# stm_board.net
KiCad netlist of a schematic drawn in EAGLE
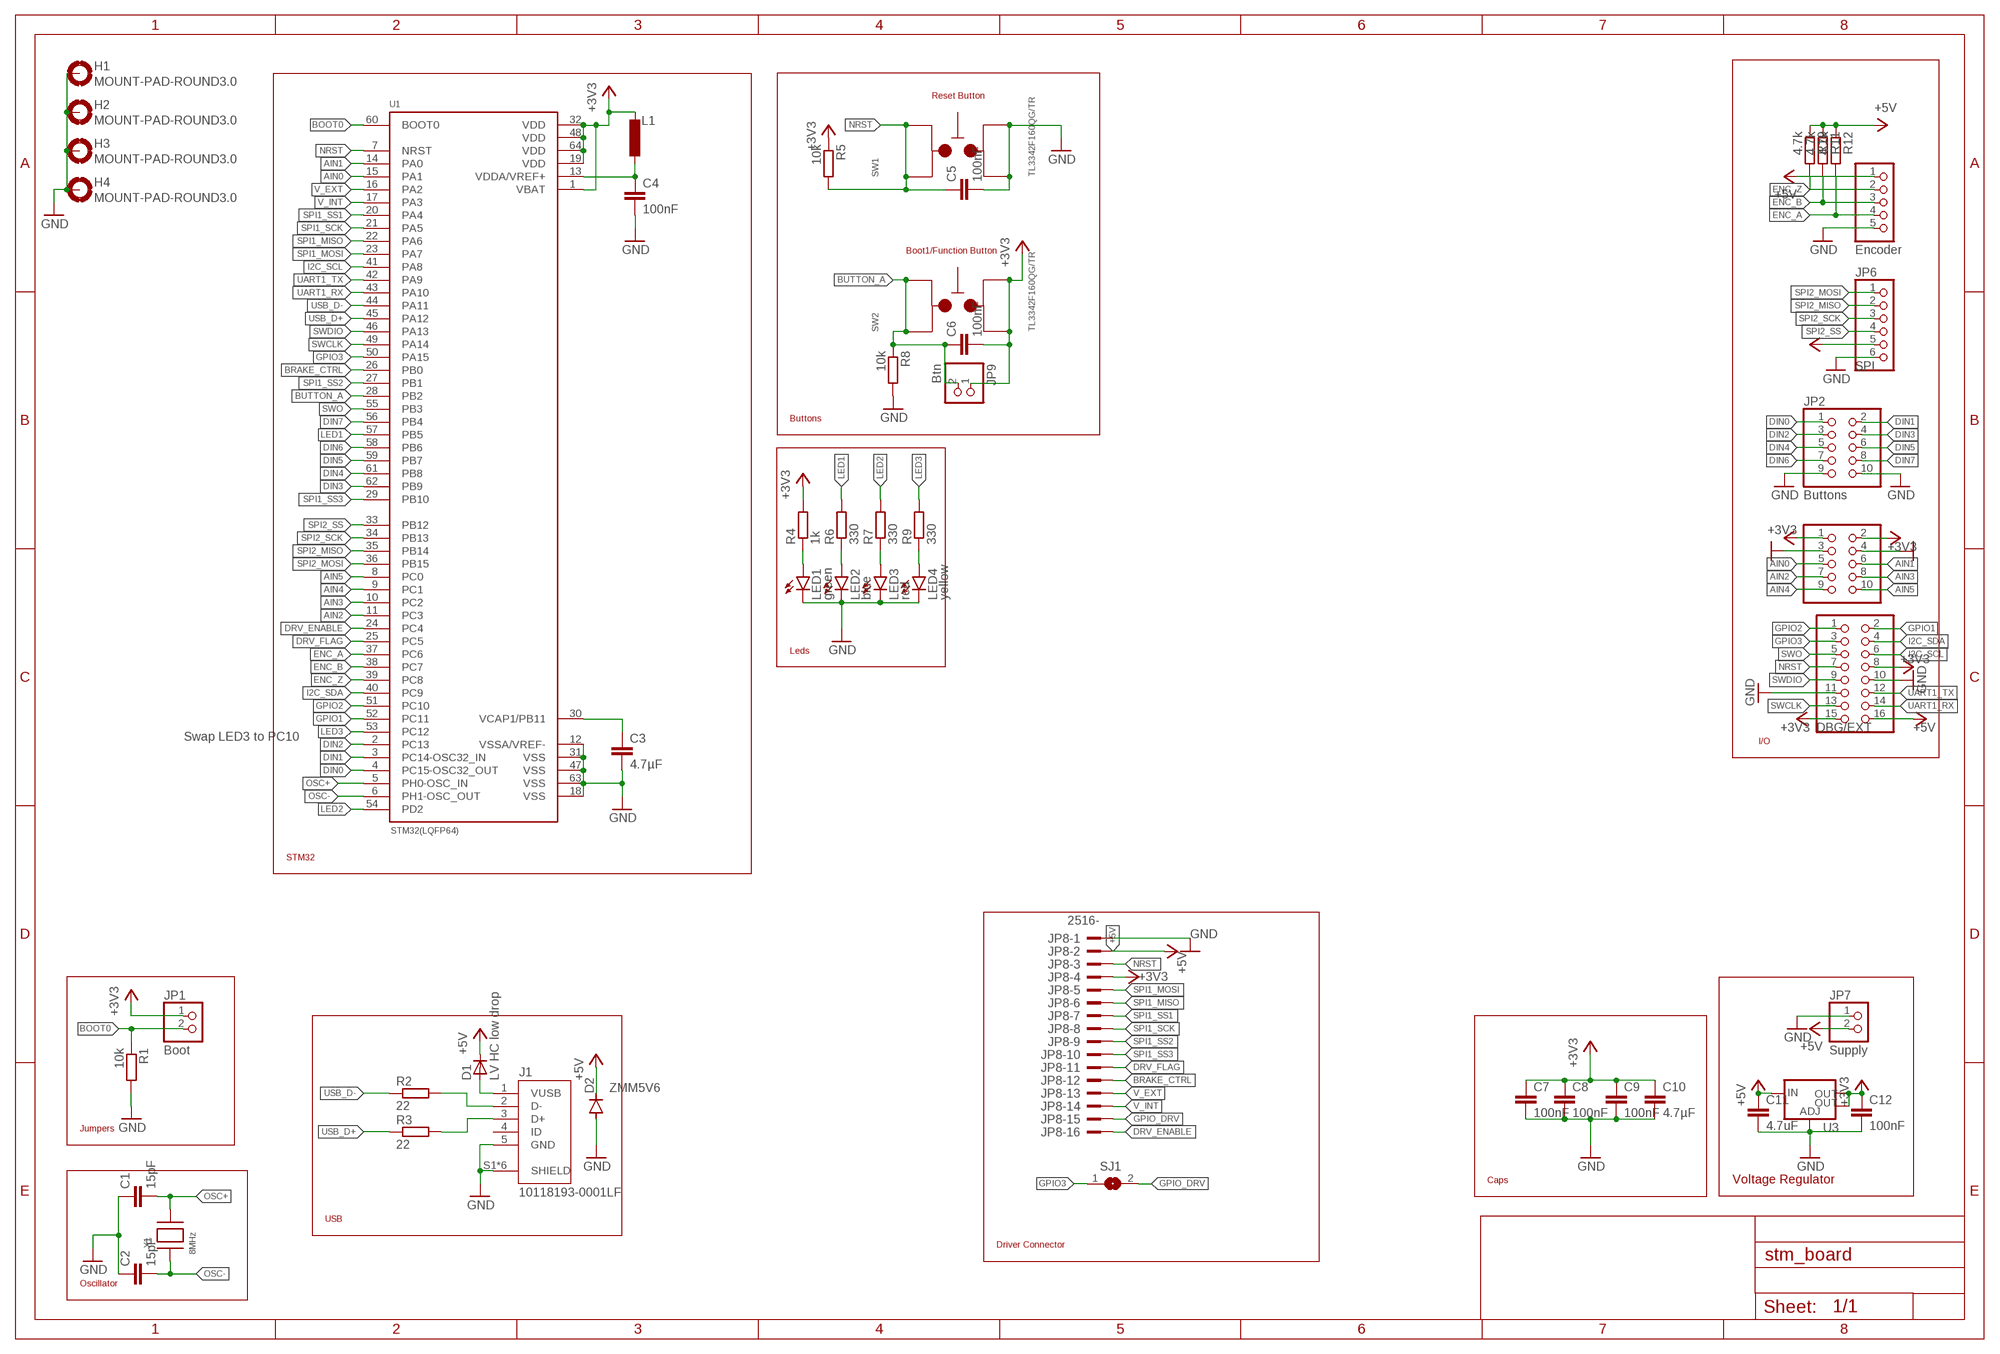
[diagram p0: schematic, sheet 1]

(export (version "E")
  (design (tool "Eeschema 10.0.6"))
  (components
    (comp (ref "C1")
      (value "15pF")
      (footprint "eagle-import:C0603")
      (libsource (lib "eagle-import") (part "C-EUC0603"))
    )
    (comp (ref "C2")
      (value "15pF")
      (footprint "eagle-import:C0603")
      (libsource (lib "eagle-import") (part "C-EUC0603"))
    )
    (comp (ref "C3")
      (value "4.7µF")
      (footprint "eagle-import:C0805")
      (libsource (lib "eagle-import") (part "C-EUC0805"))
    )
    (comp (ref "C4")
      (value "100nF")
      (footprint "eagle-import:C0603")
      (libsource (lib "eagle-import") (part "C-EUC0603"))
    )
    (comp (ref "C5")
      (value "100nF")
      (footprint "eagle-import:C0603")
      (libsource (lib "eagle-import") (part "C-EUC0603"))
    )
    (comp (ref "C6")
      (value "100nF")
      (footprint "eagle-import:C0603")
      (libsource (lib "eagle-import") (part "C-EUC0603"))
    )
    (comp (ref "C7")
      (value "100nF")
      (footprint "eagle-import:C0603")
      (libsource (lib "eagle-import") (part "C-EUC0603"))
    )
    (comp (ref "C8")
      (value "100nF")
      (footprint "eagle-import:C0603")
      (libsource (lib "eagle-import") (part "C-EUC0603"))
    )
    (comp (ref "C9")
      (value "100nF")
      (footprint "eagle-import:C0603")
      (libsource (lib "eagle-import") (part "C-EUC0603"))
    )
    (comp (ref "C10")
      (value "4.7µF")
      (footprint "eagle-import:C0805")
      (libsource (lib "eagle-import") (part "C-EUC0805"))
    )
    (comp (ref "C11")
      (value "4.7uF")
      (footprint "eagle-import:C0805")
      (libsource (lib "eagle-import") (part "C-EUC0805"))
    )
    (comp (ref "C12")
      (value "100nF")
      (footprint "eagle-import:C0603")
      (libsource (lib "eagle-import") (part "C-EUC0603"))
    )
    (comp (ref "D1")
      (value "LV HC low drop")
      (footprint "eagle-import:SMADIODE")
      (libsource (lib "eagle-import") (part "DIODESMA"))
    )
    (comp (ref "D2")
      (value "ZMM5V6")
      (footprint "eagle-import:MINIMELF")
      (libsource (lib "eagle-import") (part "DIODE-MINIMELF"))
    )
    (comp (ref "H1")
      (value "MOUNT-PAD-ROUND3.0")
      (footprint "eagle-import:3,0-PAD")
      (libsource (lib "eagle-import") (part "MOUNT-PAD-ROUND3.0"))
    )
    (comp (ref "H2")
      (value "MOUNT-PAD-ROUND3.0")
      (footprint "eagle-import:3,0-PAD")
      (libsource (lib "eagle-import") (part "MOUNT-PAD-ROUND3.0"))
    )
    (comp (ref "H3")
      (value "MOUNT-PAD-ROUND3.0")
      (footprint "eagle-import:3,0-PAD")
      (libsource (lib "eagle-import") (part "MOUNT-PAD-ROUND3.0"))
    )
    (comp (ref "H4")
      (value "MOUNT-PAD-ROUND3.0")
      (footprint "eagle-import:3,0-PAD")
      (libsource (lib "eagle-import") (part "MOUNT-PAD-ROUND3.0"))
    )
    (comp (ref "J1")
      (value "10118193-0001LF")
      (footprint "eagle-import:FCI_10118193-0001LF")
      (fields (field (name "MF") "Amphenol ICC"))
      (libsource (lib "eagle-import") (part "10118193-0001LF"))
    )
    (comp (ref "JP1")
      (value "Boot")
      (footprint "eagle-import:1X02")
      (libsource (lib "eagle-import") (part "PINHD-1X2"))
    )
    (comp (ref "JP2")
      (value "Buttons")
      (footprint "eagle-import:2X05")
      (libsource (lib "eagle-import") (part "PINHD-2X5"))
    )
    (comp (ref "JP3")
      (value "Analog")
      (footprint "eagle-import:2X05")
      (libsource (lib "eagle-import") (part "PINHD-2X5"))
    )
    (comp (ref "JP4")
      (value "DBG/EXT")
      (footprint "eagle-import:2X08")
      (libsource (lib "eagle-import") (part "PINHD-2X8"))
    )
    (comp (ref "JP5")
      (value "Encoder")
      (footprint "eagle-import:1X05")
      (libsource (lib "eagle-import") (part "PINHD-1X5"))
    )
    (comp (ref "JP6")
      (value "SPI")
      (footprint "eagle-import:1X06")
      (libsource (lib "eagle-import") (part "PINHD-1X6"))
    )
    (comp (ref "JP7")
      (value "Supply")
      (footprint "eagle-import:1X02")
      (libsource (lib "eagle-import") (part "PINHD-1X2"))
    )
    (comp (ref "JP8")
      (value "2516-")
      (footprint "eagle-import:PAK100_2500-16")
      (libsource (lib "eagle-import") (part "2516-"))
    )
    (comp (ref "JP9")
      (value "Btn")
      (footprint "eagle-import:1X02")
      (libsource (lib "eagle-import") (part "PINHD-1X2"))
    )
    (comp (ref "L1")
      (value "2.2µH")
      (footprint "eagle-import:L2012C")
      (libsource (lib "eagle-import") (part "L-EUL2012C"))
    )
    (comp (ref "LED1")
      (value "green")
      (footprint "eagle-import:CHIPLED_0805")
      (libsource (lib "eagle-import") (part "LEDCHIPLED_0805"))
    )
    (comp (ref "LED2")
      (value "blue")
      (footprint "eagle-import:CHIPLED_0805")
      (libsource (lib "eagle-import") (part "LEDCHIPLED_0805"))
    )
    (comp (ref "LED3")
      (value "red")
      (footprint "eagle-import:CHIPLED_0805")
      (libsource (lib "eagle-import") (part "LEDCHIPLED_0805"))
    )
    (comp (ref "LED4")
      (value "yellow")
      (footprint "eagle-import:CHIPLED_0805")
      (libsource (lib "eagle-import") (part "LEDCHIPLED_0805"))
    )
    (comp (ref "R1")
      (value "10k")
      (footprint "eagle-import:R0603")
      (libsource (lib "eagle-import") (part "R-EU_R0603"))
    )
    (comp (ref "R2")
      (value "22")
      (footprint "eagle-import:R0603")
      (libsource (lib "eagle-import") (part "R-EU_R0603"))
    )
    (comp (ref "R3")
      (value "22")
      (footprint "eagle-import:R0603")
      (libsource (lib "eagle-import") (part "R-EU_R0603"))
    )
    (comp (ref "R4")
      (value "1k")
      (footprint "eagle-import:R0603")
      (libsource (lib "eagle-import") (part "R-EU_R0603"))
    )
    (comp (ref "R5")
      (value "10k")
      (footprint "eagle-import:R0603")
      (libsource (lib "eagle-import") (part "R-EU_R0603"))
    )
    (comp (ref "R6")
      (value "330")
      (footprint "eagle-import:R0603")
      (libsource (lib "eagle-import") (part "R-EU_R0603"))
    )
    (comp (ref "R7")
      (value "330")
      (footprint "eagle-import:R0603")
      (libsource (lib "eagle-import") (part "R-EU_R0603"))
    )
    (comp (ref "R8")
      (value "10k")
      (footprint "eagle-import:R0603")
      (libsource (lib "eagle-import") (part "R-EU_R0603"))
    )
    (comp (ref "R9")
      (value "330")
      (footprint "eagle-import:R0603")
      (libsource (lib "eagle-import") (part "R-EU_R0603"))
    )
    (comp (ref "R10")
      (value "4.7k")
      (footprint "eagle-import:R0603")
      (libsource (lib "eagle-import") (part "R-EU_R0603"))
    )
    (comp (ref "R11")
      (value "4.7k")
      (footprint "eagle-import:R0603")
      (libsource (lib "eagle-import") (part "R-EU_R0603"))
    )
    (comp (ref "R12")
      (value "4.7k")
      (footprint "eagle-import:R0603")
      (libsource (lib "eagle-import") (part "R-EU_R0603"))
    )
    (comp (ref "SJ1") (value "SJ") (footprint "eagle-import:SJ") (libsource (lib "eagle-import") (part "SJ")))
    (comp (ref "SW1")
      (value "TL3342F160QG/TR")
      (footprint "eagle-import:TL3342F160QG_TR")
      (fields
        (field (name "DIGI_KEY_PART_NUMBER") "EG2531CT-ND")
        (field (name "MANUFACTURER") "E-Switch")
        (field (name "CREATED_BY") "PCBLayout.com")
      )
      (libsource (lib "eagle-import") (part "TL3342F160QG/TR"))
    )
    (comp (ref "SW2")
      (value "TL3342F160QG/TR")
      (footprint "eagle-import:TL3342F160QG_TR")
      (fields
        (field (name "DIGI_KEY_PART_NUMBER") "EG2531CT-ND")
        (field (name "MANUFACTURER") "E-Switch")
        (field (name "CREATED_BY") "PCBLayout.com")
      )
      (libsource (lib "eagle-import") (part "TL3342F160QG/TR"))
    )
    (comp (ref "U1")
      (value "STM32(LQFP64)")
      (footprint "eagle-import:QFP50P1200X1200X160-64N")
      (fields (field (name "MF") "STMicroelectronics") (field (name "MP") "STM32"))
      (libsource (lib "eagle-import") (part "STM32(LQFP64)"))
    )
    (comp (ref "U3")
      (value "V_REG_LM1117SOT223")
      (footprint "eagle-import:SOT223")
      (libsource (lib "eagle-import") (part "V_REG_LM1117SOT223"))
    )
    (comp (ref "X1")
      (value "8MHz")
      (footprint "eagle-import:NX5032")
      (libsource (lib "eagle-import") (part "XTALNX5032"))
    )
  )
  (nets
    (net (code "1") (name "+3V3") (class "Default")
      (node (ref "C10") (pin "1") (pinfunction "1_1") (pintype "passive"))
      (node (ref "C12") (pin "1") (pinfunction "1_1") (pintype "passive"))
      (node (ref "C6") (pin "2") (pinfunction "2_2") (pintype "passive"))
      (node (ref "C7") (pin "1") (pinfunction "1_1") (pintype "passive"))
      (node (ref "C8") (pin "1") (pinfunction "1_1") (pintype "passive"))
      (node (ref "C9") (pin "1") (pinfunction "1_1") (pintype "passive"))
      (node (ref "JP1") (pin "1") (pinfunction "1_1") (pintype "passive"))
      (node (ref "JP3") (pin "1") (pinfunction "1_1") (pintype "passive"))
      (node (ref "JP3") (pin "2") (pinfunction "2_2") (pintype "passive"))
      (node (ref "JP4") (pin "15") (pinfunction "15_15") (pintype "passive"))
      (node (ref "JP4") (pin "8") (pinfunction "8_8") (pintype "passive"))
      (node (ref "JP6") (pin "5") (pinfunction "5_5") (pintype "passive"))
      (node (ref "JP8") (pin "4") (pinfunction "KL_4") (pintype "passive"))
      (node (ref "JP9") (pin "1") (pinfunction "1_1") (pintype "passive"))
      (node (ref "L1") (pin "1") (pinfunction "1_1") (pintype "passive"))
      (node (ref "R4") (pin "2") (pinfunction "2_2") (pintype "passive"))
      (node (ref "R5") (pin "1") (pinfunction "1_1") (pintype "passive"))
      (node (ref "SW2") (pin "1") (pinfunction "1_1") (pintype "passive"))
      (node (ref "SW2") (pin "2") (pinfunction "2_2") (pintype "passive"))
      (node (ref "U1") (pin "1") (pinfunction "VBAT_1") (pintype "power_in"))
      (node (ref "U1") (pin "19") (pinfunction "VDD_19") (pintype "power_in"))
      (node (ref "U1") (pin "32") (pinfunction "VDD_32") (pintype "power_in"))
      (node (ref "U1") (pin "48") (pinfunction "VDD_48") (pintype "power_in"))
      (node (ref "U1") (pin "64") (pinfunction "VDD_64") (pintype "power_in"))
      (node (ref "U3") (pin "2") (pinfunction "OUT_2") (pintype "output"))
      (node (ref "U3") (pin "4") (pinfunction "OUT_4") (pintype "output"))
    )
    (net (code "2") (name "+5V") (class "Default")
      (node (ref "C11") (pin "1") (pinfunction "1_1") (pintype "passive"))
      (node (ref "D1") (pin "C") (pinfunction "C_C") (pintype "passive"))
      (node (ref "D2") (pin "C") (pinfunction "C_C") (pintype "passive"))
      (node (ref "JP4") (pin "16") (pinfunction "16_16") (pintype "passive"))
      (node (ref "JP5") (pin "1") (pinfunction "1_1") (pintype "passive"))
      (node (ref "JP7") (pin "2") (pinfunction "2_2") (pintype "passive"))
      (node (ref "JP8") (pin "2") (pinfunction "KL_2") (pintype "passive"))
      (node (ref "R10") (pin "1") (pinfunction "1_1") (pintype "passive"))
      (node (ref "R11") (pin "1") (pinfunction "1_1") (pintype "passive"))
      (node (ref "R12") (pin "1") (pinfunction "1_1") (pintype "passive"))
      (node (ref "U3") (pin "3") (pinfunction "IN_3") (pintype "input"))
    )
    (net (code "3") (name "AIN0") (class "Default")
      (node (ref "JP3") (pin "5") (pinfunction "5_5") (pintype "passive"))
      (node (ref "U1") (pin "15") (pinfunction "PA1_15") (pintype "bidirectional"))
    )
    (net (code "4") (name "AIN1") (class "Default")
      (node (ref "JP3") (pin "6") (pinfunction "6_6") (pintype "passive"))
      (node (ref "U1") (pin "14") (pinfunction "PA0_14") (pintype "bidirectional"))
    )
    (net (code "5") (name "AIN2") (class "Default")
      (node (ref "JP3") (pin "7") (pinfunction "7_7") (pintype "passive"))
      (node (ref "U1") (pin "11") (pinfunction "PC3_11") (pintype "bidirectional"))
    )
    (net (code "6") (name "AIN3") (class "Default")
      (node (ref "JP3") (pin "8") (pinfunction "8_8") (pintype "passive"))
      (node (ref "U1") (pin "10") (pinfunction "PC2_10") (pintype "bidirectional"))
    )
    (net (code "7") (name "AIN4") (class "Default")
      (node (ref "JP3") (pin "9") (pinfunction "9_9") (pintype "passive"))
      (node (ref "U1") (pin "9") (pinfunction "PC1_9") (pintype "bidirectional"))
    )
    (net (code "8") (name "AIN5") (class "Default")
      (node (ref "JP3") (pin "10") (pinfunction "10_10") (pintype "passive"))
      (node (ref "U1") (pin "8") (pinfunction "PC0_8") (pintype "bidirectional"))
    )
    (net (code "9") (name "BOOT0") (class "Default")
      (node (ref "JP1") (pin "2") (pinfunction "2_2") (pintype "passive"))
      (node (ref "R1") (pin "1") (pinfunction "1_1") (pintype "passive"))
      (node (ref "U1") (pin "60") (pinfunction "BOOT0_60") (pintype "input"))
    )
    (net (code "10") (name "BRAKE_CTRL") (class "Default")
      (node (ref "JP8") (pin "12") (pinfunction "KL_12") (pintype "passive"))
      (node (ref "U1") (pin "26") (pinfunction "PB0_26") (pintype "bidirectional"))
    )
    (net (code "11") (name "BUTTON_A") (class "Default")
      (node (ref "C6") (pin "1") (pinfunction "1_1") (pintype "passive"))
      (node (ref "JP9") (pin "2") (pinfunction "2_2") (pintype "passive"))
      (node (ref "R8") (pin "1") (pinfunction "1_1") (pintype "passive"))
      (node (ref "SW2") (pin "3") (pinfunction "3_3") (pintype "passive"))
      (node (ref "SW2") (pin "4") (pinfunction "4_4") (pintype "passive"))
      (node (ref "U1") (pin "28") (pinfunction "PB2_28") (pintype "bidirectional"))
    )
    (net (code "12") (name "DIN0") (class "Default")
      (node (ref "JP2") (pin "1") (pinfunction "1_1") (pintype "passive"))
      (node (ref "U1") (pin "4") (pinfunction "PC15-OSC32_OUT_4") (pintype "bidirectional"))
    )
    (net (code "13") (name "DIN1") (class "Default")
      (node (ref "JP2") (pin "2") (pinfunction "2_2") (pintype "passive"))
      (node (ref "U1") (pin "3") (pinfunction "PC14-OSC32_IN_3") (pintype "bidirectional"))
    )
    (net (code "14") (name "DIN2") (class "Default")
      (node (ref "JP2") (pin "3") (pinfunction "3_3") (pintype "passive"))
      (node (ref "U1") (pin "2") (pinfunction "PC13_2") (pintype "bidirectional"))
    )
    (net (code "15") (name "DIN3") (class "Default")
      (node (ref "JP2") (pin "4") (pinfunction "4_4") (pintype "passive"))
      (node (ref "U1") (pin "62") (pinfunction "PB9_62") (pintype "bidirectional"))
    )
    (net (code "16") (name "DIN4") (class "Default")
      (node (ref "JP2") (pin "5") (pinfunction "5_5") (pintype "passive"))
      (node (ref "U1") (pin "61") (pinfunction "PB8_61") (pintype "bidirectional"))
    )
    (net (code "17") (name "DIN5") (class "Default")
      (node (ref "JP2") (pin "6") (pinfunction "6_6") (pintype "passive"))
      (node (ref "U1") (pin "59") (pinfunction "PB7_59") (pintype "bidirectional"))
    )
    (net (code "18") (name "DIN6") (class "Default")
      (node (ref "JP2") (pin "7") (pinfunction "7_7") (pintype "passive"))
      (node (ref "U1") (pin "58") (pinfunction "PB6_58") (pintype "bidirectional"))
    )
    (net (code "19") (name "DIN7") (class "Default")
      (node (ref "JP2") (pin "8") (pinfunction "8_8") (pintype "passive"))
      (node (ref "U1") (pin "56") (pinfunction "PB4_56") (pintype "bidirectional"))
    )
    (net (code "20") (name "DRV_ENABLE") (class "Default")
      (node (ref "JP8") (pin "16") (pinfunction "KL_16") (pintype "passive"))
      (node (ref "U1") (pin "24") (pinfunction "PC4_24") (pintype "bidirectional"))
    )
    (net (code "21") (name "DRV_FLAG") (class "Default")
      (node (ref "JP8") (pin "11") (pinfunction "KL_11") (pintype "passive"))
      (node (ref "U1") (pin "25") (pinfunction "PC5_25") (pintype "bidirectional"))
    )
    (net (code "22") (name "ENC_A") (class "Default")
      (node (ref "JP5") (pin "4") (pinfunction "4_4") (pintype "passive"))
      (node (ref "R12") (pin "2") (pinfunction "2_2") (pintype "passive"))
      (node (ref "U1") (pin "37") (pinfunction "PC6_37") (pintype "bidirectional"))
    )
    (net (code "23") (name "ENC_B") (class "Default")
      (node (ref "JP5") (pin "3") (pinfunction "3_3") (pintype "passive"))
      (node (ref "R11") (pin "2") (pinfunction "2_2") (pintype "passive"))
      (node (ref "U1") (pin "38") (pinfunction "PC7_38") (pintype "bidirectional"))
    )
    (net (code "24") (name "ENC_Z") (class "Default")
      (node (ref "JP5") (pin "2") (pinfunction "2_2") (pintype "passive"))
      (node (ref "R10") (pin "2") (pinfunction "2_2") (pintype "passive"))
      (node (ref "U1") (pin "39") (pinfunction "PC8_39") (pintype "bidirectional"))
    )
    (net (code "25") (name "GND") (class "Default")
      (node (ref "C1") (pin "1") (pinfunction "1_1") (pintype "passive"))
      (node (ref "C10") (pin "2") (pinfunction "2_2") (pintype "passive"))
      (node (ref "C11") (pin "2") (pinfunction "2_2") (pintype "passive"))
      (node (ref "C12") (pin "2") (pinfunction "2_2") (pintype "passive"))
      (node (ref "C2") (pin "1") (pinfunction "1_1") (pintype "passive"))
      (node (ref "C3") (pin "2") (pinfunction "2_2") (pintype "passive"))
      (node (ref "C4") (pin "2") (pinfunction "2_2") (pintype "passive"))
      (node (ref "C5") (pin "2") (pinfunction "2_2") (pintype "passive"))
      (node (ref "C7") (pin "2") (pinfunction "2_2") (pintype "passive"))
      (node (ref "C8") (pin "2") (pinfunction "2_2") (pintype "passive"))
      (node (ref "C9") (pin "2") (pinfunction "2_2") (pintype "passive"))
      (node (ref "D2") (pin "A") (pinfunction "A_A") (pintype "passive"))
      (node (ref "H1") (pin "B3,0") (pinfunction "MOUNT_B3,0") (pintype "passive"))
      (node (ref "H2") (pin "B3,0") (pinfunction "MOUNT_B3,0") (pintype "passive"))
      (node (ref "H3") (pin "B3,0") (pinfunction "MOUNT_B3,0") (pintype "passive"))
      (node (ref "H4") (pin "B3,0") (pinfunction "MOUNT_B3,0") (pintype "passive"))
      (node (ref "J1") (pin "5") (pinfunction "GND_5") (pintype "passive"))
      (node (ref "J1") (pin "S1") (pinfunction "SHIELD_S1") (pintype "passive"))
      (node (ref "J1") (pin "S2") (pinfunction "SHIELD_S2") (pintype "passive"))
      (node (ref "J1") (pin "S3") (pinfunction "SHIELD_S3") (pintype "passive"))
      (node (ref "J1") (pin "S4") (pinfunction "SHIELD_S4") (pintype "passive"))
      (node (ref "J1") (pin "S5") (pinfunction "SHIELD_S5") (pintype "passive"))
      (node (ref "J1") (pin "S6") (pinfunction "SHIELD_S6") (pintype "passive"))
      (node (ref "JP2") (pin "10") (pinfunction "10_10") (pintype "passive"))
      (node (ref "JP2") (pin "9") (pinfunction "9_9") (pintype "passive"))
      (node (ref "JP3") (pin "3") (pinfunction "3_3") (pintype "passive"))
      (node (ref "JP3") (pin "4") (pinfunction "4_4") (pintype "passive"))
      (node (ref "JP4") (pin "10") (pinfunction "10_10") (pintype "passive"))
      (node (ref "JP4") (pin "11") (pinfunction "11_11") (pintype "passive"))
      (node (ref "JP5") (pin "5") (pinfunction "5_5") (pintype "passive"))
      (node (ref "JP6") (pin "6") (pinfunction "6_6") (pintype "passive"))
      (node (ref "JP7") (pin "1") (pinfunction "1_1") (pintype "passive"))
      (node (ref "JP8") (pin "1") (pinfunction "KL_1") (pintype "passive"))
      (node (ref "LED1") (pin "C") (pinfunction "C_C") (pintype "passive"))
      (node (ref "LED2") (pin "C") (pinfunction "C_C") (pintype "passive"))
      (node (ref "LED3") (pin "C") (pinfunction "C_C") (pintype "passive"))
      (node (ref "LED4") (pin "C") (pinfunction "C_C") (pintype "passive"))
      (node (ref "R1") (pin "2") (pinfunction "2_2") (pintype "passive"))
      (node (ref "R8") (pin "2") (pinfunction "2_2") (pintype "passive"))
      (node (ref "SW1") (pin "1") (pinfunction "1_1") (pintype "passive"))
      (node (ref "SW1") (pin "2") (pinfunction "2_2") (pintype "passive"))
      (node (ref "U1") (pin "12") (pinfunction "VSSA/VREF-_12") (pintype "power_in"))
      (node (ref "U1") (pin "18") (pinfunction "VSS_18") (pintype "power_in"))
      (node (ref "U1") (pin "31") (pinfunction "VSS_31") (pintype "power_in"))
      (node (ref "U1") (pin "47") (pinfunction "VSS_47") (pintype "power_in"))
      (node (ref "U1") (pin "63") (pinfunction "VSS_63") (pintype "power_in"))
      (node (ref "U3") (pin "1") (pinfunction "ADJ_1") (pintype "input"))
    )
    (net (code "26") (name "GPIO1") (class "Default")
      (node (ref "JP4") (pin "2") (pinfunction "2_2") (pintype "passive"))
      (node (ref "U1") (pin "52") (pinfunction "PC11_52") (pintype "bidirectional"))
    )
    (net (code "27") (name "GPIO2") (class "Default")
      (node (ref "JP4") (pin "1") (pinfunction "1_1") (pintype "passive"))
      (node (ref "U1") (pin "51") (pinfunction "PC10_51") (pintype "bidirectional"))
    )
    (net (code "28") (name "GPIO3") (class "Default")
      (node (ref "JP4") (pin "3") (pinfunction "3_3") (pintype "passive"))
      (node (ref "SJ1") (pin "1") (pinfunction "1_1") (pintype "passive"))
      (node (ref "U1") (pin "50") (pinfunction "PA15_50") (pintype "bidirectional"))
    )
    (net (code "29") (name "GPIO_DRV") (class "Default")
      (node (ref "JP8") (pin "15") (pinfunction "KL_15") (pintype "passive"))
      (node (ref "SJ1") (pin "2") (pinfunction "2_2") (pintype "passive"))
    )
    (net (code "30") (name "I2C_SCL") (class "Default")
      (node (ref "JP4") (pin "6") (pinfunction "6_6") (pintype "passive"))
      (node (ref "U1") (pin "41") (pinfunction "PA8_41") (pintype "bidirectional"))
    )
    (net (code "31") (name "I2C_SDA") (class "Default")
      (node (ref "JP4") (pin "4") (pinfunction "4_4") (pintype "passive"))
      (node (ref "U1") (pin "40") (pinfunction "PC9_40") (pintype "bidirectional"))
    )
    (net (code "32") (name "LED1") (class "Default")
      (node (ref "R6") (pin "2") (pinfunction "2_2") (pintype "passive"))
      (node (ref "U1") (pin "57") (pinfunction "PB5_57") (pintype "bidirectional"))
    )
    (net (code "33") (name "LED2") (class "Default")
      (node (ref "R7") (pin "2") (pinfunction "2_2") (pintype "passive"))
      (node (ref "U1") (pin "54") (pinfunction "PD2_54") (pintype "bidirectional"))
    )
    (net (code "34") (name "LED3") (class "Default")
      (node (ref "R9") (pin "2") (pinfunction "2_2") (pintype "passive"))
      (node (ref "U1") (pin "53") (pinfunction "PC12_53") (pintype "bidirectional"))
    )
    (net (code "35") (name "NRST") (class "Default")
      (node (ref "C5") (pin "1") (pinfunction "1_1") (pintype "passive"))
      (node (ref "JP4") (pin "7") (pinfunction "7_7") (pintype "passive"))
      (node (ref "JP8") (pin "3") (pinfunction "KL_3") (pintype "passive"))
      (node (ref "R5") (pin "2") (pinfunction "2_2") (pintype "passive"))
      (node (ref "SW1") (pin "3") (pinfunction "3_3") (pintype "passive"))
      (node (ref "SW1") (pin "4") (pinfunction "4_4") (pintype "passive"))
      (node (ref "U1") (pin "7") (pinfunction "NRST_7") (pintype "bidirectional"))
    )
    (net (code "36") (name "Net-(J1-D+)") (class "Default")
      (node (ref "J1") (pin "3") (pinfunction "D+_3") (pintype "passive"))
      (node (ref "R3") (pin "2") (pinfunction "2_2") (pintype "passive"))
    )
    (net (code "37") (name "Net-(J1-D-)") (class "Default")
      (node (ref "J1") (pin "2") (pinfunction "D-_2") (pintype "passive"))
      (node (ref "R2") (pin "2") (pinfunction "2_2") (pintype "passive"))
    )
    (net (code "38") (name "Net-(J1-VUSB)") (class "Default")
      (node (ref "D1") (pin "A") (pinfunction "A_A") (pintype "passive"))
      (node (ref "J1") (pin "1") (pinfunction "VUSB_1") (pintype "passive"))
    )
    (net (code "39") (name "Net-(LED1-PadA)") (class "Default")
      (node (ref "LED1") (pin "A") (pinfunction "A_A") (pintype "passive"))
      (node (ref "R4") (pin "1") (pinfunction "1_1") (pintype "passive"))
    )
    (net (code "40") (name "Net-(LED2-PadA)") (class "Default")
      (node (ref "LED2") (pin "A") (pinfunction "A_A") (pintype "passive"))
      (node (ref "R6") (pin "1") (pinfunction "1_1") (pintype "passive"))
    )
    (net (code "41") (name "Net-(LED3-PadA)") (class "Default")
      (node (ref "LED3") (pin "A") (pinfunction "A_A") (pintype "passive"))
      (node (ref "R7") (pin "1") (pinfunction "1_1") (pintype "passive"))
    )
    (net (code "42") (name "Net-(LED4-PadA)") (class "Default")
      (node (ref "LED4") (pin "A") (pinfunction "A_A") (pintype "passive"))
      (node (ref "R9") (pin "1") (pinfunction "1_1") (pintype "passive"))
    )
    (net (code "43") (name "Net-(U1-VCAP1{slash}PB11)") (class "Default")
      (node (ref "C3") (pin "1") (pinfunction "1_1") (pintype "passive"))
      (node (ref "U1") (pin "30") (pinfunction "VCAP1/PB11_30") (pintype "passive"))
    )
    (net (code "44") (name "Net-(U1-VDDA{slash}VREF+)") (class "Default")
      (node (ref "C4") (pin "1") (pinfunction "1_1") (pintype "passive"))
      (node (ref "L1") (pin "2") (pinfunction "2_2") (pintype "passive"))
      (node (ref "U1") (pin "13") (pinfunction "VDDA/VREF+_13") (pintype "power_in"))
    )
    (net (code "45") (name "OSC+") (class "Default")
      (node (ref "C1") (pin "2") (pinfunction "2_2") (pintype "passive"))
      (node (ref "U1") (pin "5") (pinfunction "PH0-OSC_IN_5") (pintype "bidirectional"))
      (node (ref "X1") (pin "P$2") (pinfunction "P$2_P$2") (pintype "bidirectional"))
    )
    (net (code "46") (name "OSC-") (class "Default")
      (node (ref "C2") (pin "2") (pinfunction "2_2") (pintype "passive"))
      (node (ref "U1") (pin "6") (pinfunction "PH1-OSC_OUT_6") (pintype "bidirectional"))
      (node (ref "X1") (pin "P$1") (pinfunction "P$1_P$1") (pintype "bidirectional"))
    )
    (net (code "47") (name "SPI1_MISO") (class "Default")
      (node (ref "JP8") (pin "6") (pinfunction "KL_6") (pintype "passive"))
      (node (ref "U1") (pin "22") (pinfunction "PA6_22") (pintype "bidirectional"))
    )
    (net (code "48") (name "SPI1_MOSI") (class "Default")
      (node (ref "JP8") (pin "5") (pinfunction "KL_5") (pintype "passive"))
      (node (ref "U1") (pin "23") (pinfunction "PA7_23") (pintype "bidirectional"))
    )
    (net (code "49") (name "SPI1_SCK") (class "Default")
      (node (ref "JP8") (pin "8") (pinfunction "KL_8") (pintype "passive"))
      (node (ref "U1") (pin "21") (pinfunction "PA5_21") (pintype "bidirectional"))
    )
    (net (code "50") (name "SPI1_SS1") (class "Default")
      (node (ref "JP8") (pin "7") (pinfunction "KL_7") (pintype "passive"))
      (node (ref "U1") (pin "20") (pinfunction "PA4_20") (pintype "bidirectional"))
    )
    (net (code "51") (name "SPI1_SS2") (class "Default")
      (node (ref "JP8") (pin "9") (pinfunction "KL_9") (pintype "passive"))
      (node (ref "U1") (pin "27") (pinfunction "PB1_27") (pintype "bidirectional"))
    )
    (net (code "52") (name "SPI1_SS3") (class "Default")
      (node (ref "JP8") (pin "10") (pinfunction "KL_10") (pintype "passive"))
      (node (ref "U1") (pin "29") (pinfunction "PB10_29") (pintype "bidirectional"))
    )
    (net (code "53") (name "SPI2_MISO") (class "Default")
      (node (ref "JP6") (pin "2") (pinfunction "2_2") (pintype "passive"))
      (node (ref "U1") (pin "35") (pinfunction "PB14_35") (pintype "bidirectional"))
    )
    (net (code "54") (name "SPI2_MOSI") (class "Default")
      (node (ref "JP6") (pin "1") (pinfunction "1_1") (pintype "passive"))
      (node (ref "U1") (pin "36") (pinfunction "PB15_36") (pintype "bidirectional"))
    )
    (net (code "55") (name "SPI2_SCK") (class "Default")
      (node (ref "JP6") (pin "3") (pinfunction "3_3") (pintype "passive"))
      (node (ref "U1") (pin "34") (pinfunction "PB13_34") (pintype "bidirectional"))
    )
    (net (code "56") (name "SPI2_SS") (class "Default")
      (node (ref "JP6") (pin "4") (pinfunction "4_4") (pintype "passive"))
      (node (ref "U1") (pin "33") (pinfunction "PB12_33") (pintype "bidirectional"))
    )
    (net (code "57") (name "SWCLK") (class "Default")
      (node (ref "JP4") (pin "13") (pinfunction "13_13") (pintype "passive"))
      (node (ref "U1") (pin "49") (pinfunction "PA14_49") (pintype "bidirectional"))
    )
    (net (code "58") (name "SWDIO") (class "Default")
      (node (ref "JP4") (pin "9") (pinfunction "9_9") (pintype "passive"))
      (node (ref "U1") (pin "46") (pinfunction "PA13_46") (pintype "bidirectional"))
    )
    (net (code "59") (name "SWO") (class "Default")
      (node (ref "JP4") (pin "5") (pinfunction "5_5") (pintype "passive"))
      (node (ref "U1") (pin "55") (pinfunction "PB3_55") (pintype "bidirectional"))
    )
    (net (code "60") (name "UART1_RX") (class "Default")
      (node (ref "JP4") (pin "14") (pinfunction "14_14") (pintype "passive"))
      (node (ref "U1") (pin "43") (pinfunction "PA10_43") (pintype "bidirectional"))
    )
    (net (code "61") (name "UART1_TX") (class "Default")
      (node (ref "JP4") (pin "12") (pinfunction "12_12") (pintype "passive"))
      (node (ref "U1") (pin "42") (pinfunction "PA9_42") (pintype "bidirectional"))
    )
    (net (code "62") (name "USB_D+") (class "Default")
      (node (ref "R3") (pin "1") (pinfunction "1_1") (pintype "passive"))
      (node (ref "U1") (pin "45") (pinfunction "PA12_45") (pintype "bidirectional"))
    )
    (net (code "63") (name "USB_D-") (class "Default")
      (node (ref "R2") (pin "1") (pinfunction "1_1") (pintype "passive"))
      (node (ref "U1") (pin "44") (pinfunction "PA11_44") (pintype "bidirectional"))
    )
    (net (code "64") (name "V_EXT") (class "Default")
      (node (ref "JP8") (pin "13") (pinfunction "KL_13") (pintype "passive"))
      (node (ref "U1") (pin "16") (pinfunction "PA2_16") (pintype "bidirectional"))
    )
    (net (code "65") (name "V_INT") (class "Default")
      (node (ref "JP8") (pin "14") (pinfunction "KL_14") (pintype "passive"))
      (node (ref "U1") (pin "17") (pinfunction "PA3_17") (pintype "bidirectional"))
    )
    (net (code "66") (name "unconnected-(J1-ID-Pad4)") (class "Default")
      (node (ref "J1") (pin "4") (pinfunction "ID_4") (pintype "passive"))
    )
  )
)
